# controller.net
KiCad netlist of a schematic drawn in EAGLE
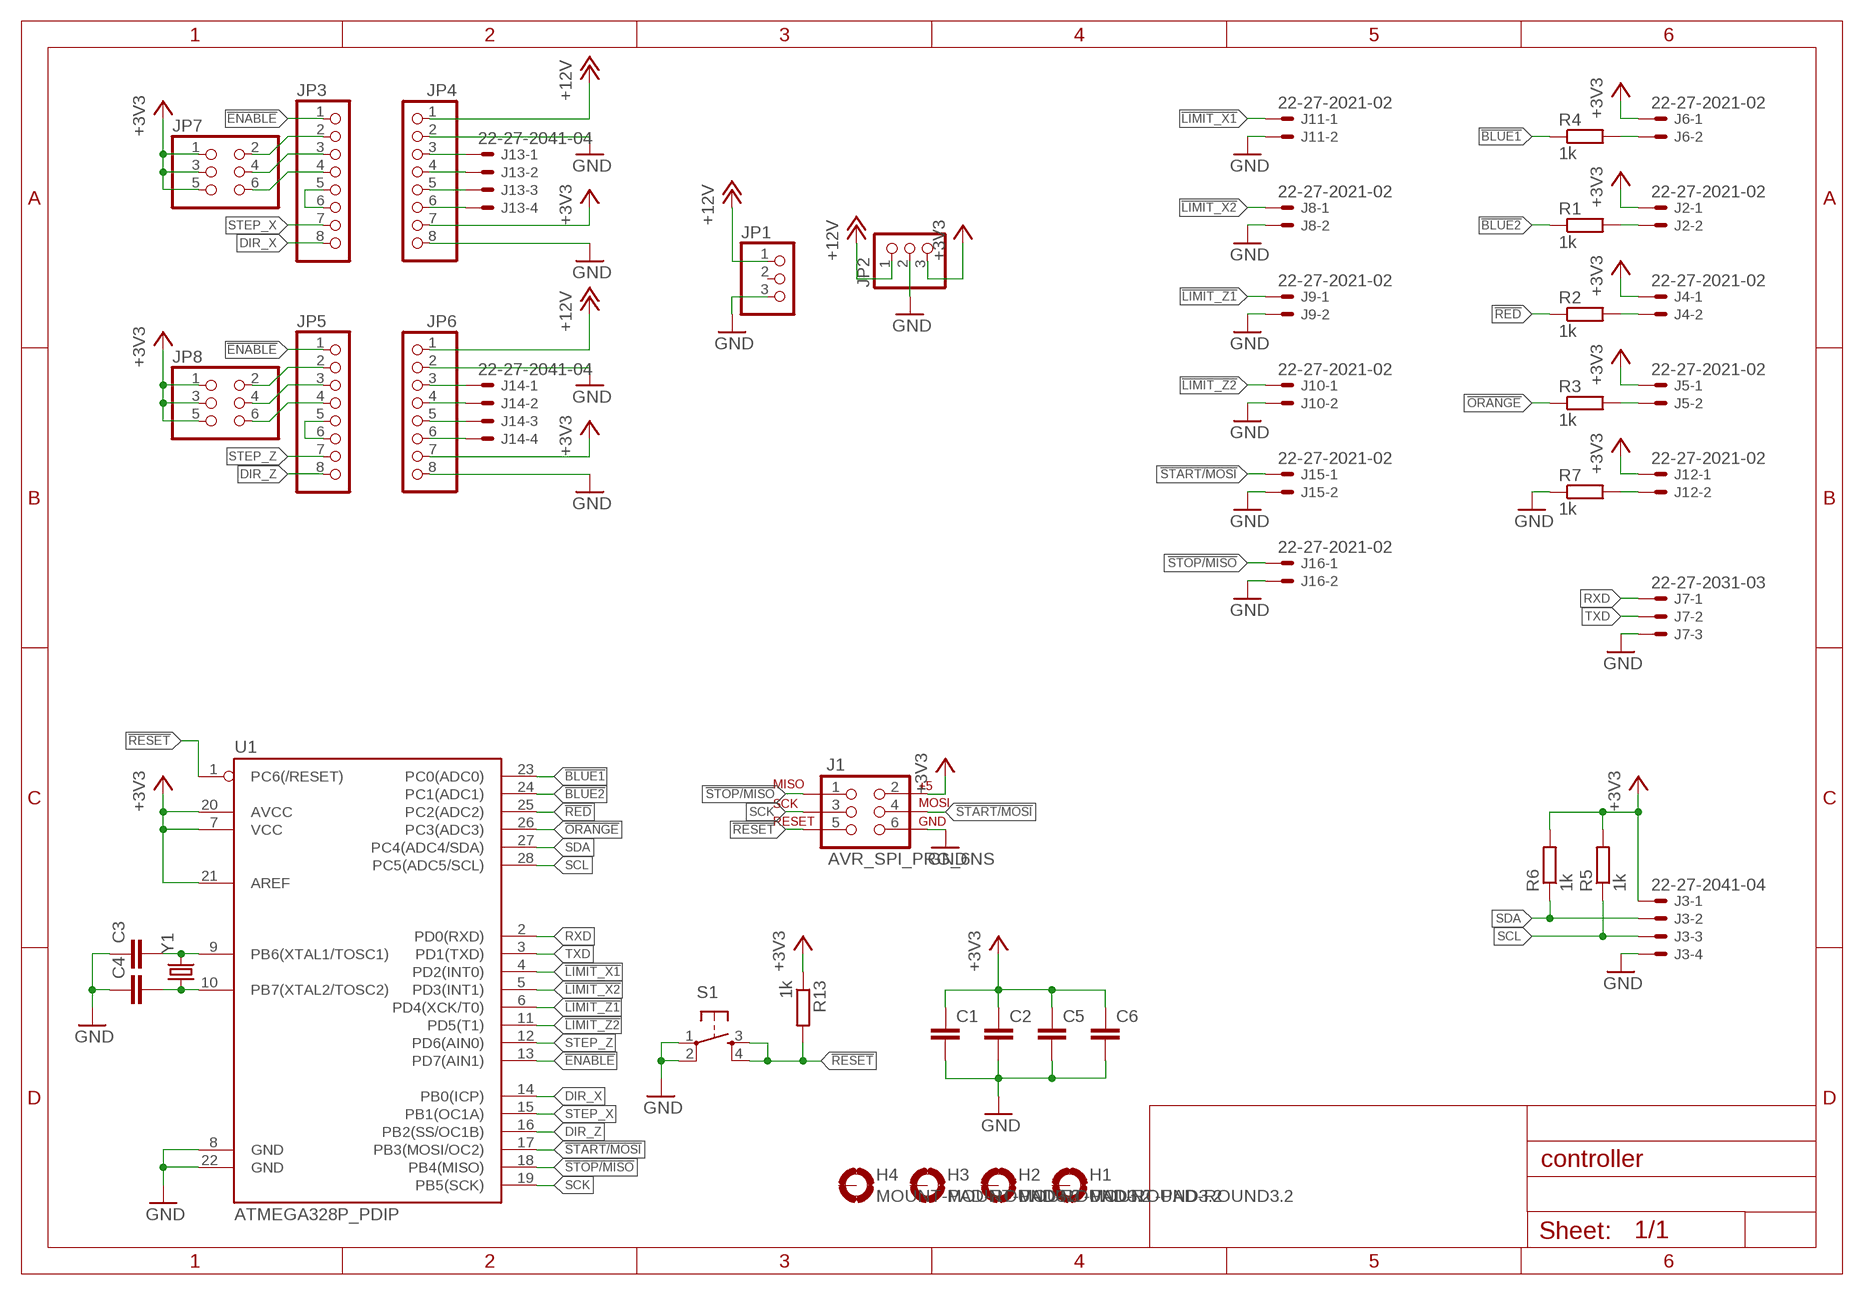
[diagram p0: schematic, sheet 1]

(export (version "E")
  (design (tool "Eeschema 10.0.6"))
  (components
    (comp (ref "C1")
      (value "C-EUC0603")
      (footprint "eagle-import:C0603")
      (libsource (lib "eagle-import") (part "C-EUC0603"))
    )
    (comp (ref "C2")
      (value "C-EUC0603")
      (footprint "eagle-import:C0603")
      (libsource (lib "eagle-import") (part "C-EUC0603"))
    )
    (comp (ref "C3")
      (value "C-EUC0603K")
      (footprint "eagle-import:C0603K")
      (libsource (lib "eagle-import") (part "C-EUC0603K"))
    )
    (comp (ref "C4")
      (value "C-EUC0603K")
      (footprint "eagle-import:C0603K")
      (libsource (lib "eagle-import") (part "C-EUC0603K"))
    )
    (comp (ref "C5")
      (value "C-EUC0603")
      (footprint "eagle-import:C0603")
      (libsource (lib "eagle-import") (part "C-EUC0603"))
    )
    (comp (ref "C6")
      (value "C-EUC0603")
      (footprint "eagle-import:C0603")
      (libsource (lib "eagle-import") (part "C-EUC0603"))
    )
    (comp (ref "H1")
      (value "MOUNT-PAD-ROUND3.2")
      (footprint "eagle-import:3,2-PAD")
      (libsource (lib "eagle-import") (part "MOUNT-PAD-ROUND3.2"))
    )
    (comp (ref "H2")
      (value "MOUNT-PAD-ROUND3.2")
      (footprint "eagle-import:3,2-PAD")
      (libsource (lib "eagle-import") (part "MOUNT-PAD-ROUND3.2"))
    )
    (comp (ref "H3")
      (value "MOUNT-PAD-ROUND3.2")
      (footprint "eagle-import:3,2-PAD")
      (libsource (lib "eagle-import") (part "MOUNT-PAD-ROUND3.2"))
    )
    (comp (ref "H4")
      (value "MOUNT-PAD-ROUND3.2")
      (footprint "eagle-import:3,2-PAD")
      (libsource (lib "eagle-import") (part "MOUNT-PAD-ROUND3.2"))
    )
    (comp (ref "J1")
      (value "AVR_SPI_PRG_6NS")
      (footprint "eagle-import:2X3-NS")
      (libsource (lib "eagle-import") (part "AVR_SPI_PRG_6NS"))
    )
    (comp (ref "J2")
      (value "22-27-2021-02")
      (footprint "eagle-import:6410-02")
      (libsource (lib "eagle-import") (part "22-?-0227-2021"))
    )
    (comp (ref "J3")
      (value "22-27-2041-04")
      (footprint "eagle-import:6410-04")
      (libsource (lib "eagle-import") (part "22-?-0427-2041"))
    )
    (comp (ref "J4")
      (value "22-27-2021-02")
      (footprint "eagle-import:6410-02")
      (libsource (lib "eagle-import") (part "22-?-0227-2021"))
    )
    (comp (ref "J5")
      (value "22-27-2021-02")
      (footprint "eagle-import:6410-02")
      (libsource (lib "eagle-import") (part "22-?-0227-2021"))
    )
    (comp (ref "J6")
      (value "22-27-2021-02")
      (footprint "eagle-import:6410-02")
      (libsource (lib "eagle-import") (part "22-?-0227-2021"))
    )
    (comp (ref "J7")
      (value "22-27-2031-03")
      (footprint "eagle-import:6410-03")
      (libsource (lib "eagle-import") (part "22-?-0327-2031"))
    )
    (comp (ref "J8")
      (value "22-27-2021-02")
      (footprint "eagle-import:6410-02")
      (libsource (lib "eagle-import") (part "22-?-0227-2021"))
    )
    (comp (ref "J9")
      (value "22-27-2021-02")
      (footprint "eagle-import:6410-02")
      (libsource (lib "eagle-import") (part "22-?-0227-2021"))
    )
    (comp (ref "J10")
      (value "22-27-2021-02")
      (footprint "eagle-import:6410-02")
      (libsource (lib "eagle-import") (part "22-?-0227-2021"))
    )
    (comp (ref "J11")
      (value "22-27-2021-02")
      (footprint "eagle-import:6410-02")
      (libsource (lib "eagle-import") (part "22-?-0227-2021"))
    )
    (comp (ref "J12")
      (value "22-27-2021-02")
      (footprint "eagle-import:6410-02")
      (libsource (lib "eagle-import") (part "22-?-0227-2021"))
    )
    (comp (ref "J13")
      (value "22-27-2041-04")
      (footprint "eagle-import:6410-04")
      (libsource (lib "eagle-import") (part "22-?-0427-2041"))
    )
    (comp (ref "J14")
      (value "22-27-2041-04")
      (footprint "eagle-import:6410-04")
      (libsource (lib "eagle-import") (part "22-?-0427-2041"))
    )
    (comp (ref "J15")
      (value "22-27-2021-02")
      (footprint "eagle-import:6410-02")
      (libsource (lib "eagle-import") (part "22-?-0227-2021"))
    )
    (comp (ref "J16")
      (value "22-27-2021-02")
      (footprint "eagle-import:6410-02")
      (libsource (lib "eagle-import") (part "22-?-0227-2021"))
    )
    (comp (ref "JP1")
      (value "PINHD-1X3")
      (footprint "eagle-import:1X03")
      (libsource (lib "eagle-import") (part "PINHD-1X3"))
    )
    (comp (ref "JP2")
      (value "PINHD-1X3")
      (footprint "eagle-import:1X03")
      (libsource (lib "eagle-import") (part "PINHD-1X3"))
    )
    (comp (ref "JP3")
      (value "PINHD-1X8")
      (footprint "eagle-import:1X08")
      (libsource (lib "eagle-import") (part "PINHD-1X8"))
    )
    (comp (ref "JP4")
      (value "PINHD-1X8")
      (footprint "eagle-import:1X08")
      (libsource (lib "eagle-import") (part "PINHD-1X8"))
    )
    (comp (ref "JP5")
      (value "PINHD-1X8")
      (footprint "eagle-import:1X08")
      (libsource (lib "eagle-import") (part "PINHD-1X8"))
    )
    (comp (ref "JP6")
      (value "PINHD-1X8")
      (footprint "eagle-import:1X08")
      (libsource (lib "eagle-import") (part "PINHD-1X8"))
    )
    (comp (ref "JP7")
      (value "PINHD-2X3")
      (footprint "eagle-import:2X03")
      (libsource (lib "eagle-import") (part "PINHD-2X3"))
    )
    (comp (ref "JP8")
      (value "PINHD-2X3")
      (footprint "eagle-import:2X03")
      (libsource (lib "eagle-import") (part "PINHD-2X3"))
    )
    (comp (ref "R1")
      (value "1k")
      (footprint "eagle-import:R0603")
      (libsource (lib "eagle-import") (part "R-EU_R0603"))
    )
    (comp (ref "R2")
      (value "1k")
      (footprint "eagle-import:R0603")
      (libsource (lib "eagle-import") (part "R-EU_R0603"))
    )
    (comp (ref "R3")
      (value "1k")
      (footprint "eagle-import:R0603")
      (libsource (lib "eagle-import") (part "R-EU_R0603"))
    )
    (comp (ref "R4")
      (value "1k")
      (footprint "eagle-import:R0603")
      (libsource (lib "eagle-import") (part "R-EU_R0603"))
    )
    (comp (ref "R5")
      (value "1k")
      (footprint "eagle-import:R0603")
      (libsource (lib "eagle-import") (part "R-EU_R0603"))
    )
    (comp (ref "R6")
      (value "1k")
      (footprint "eagle-import:R0603")
      (libsource (lib "eagle-import") (part "R-EU_R0603"))
    )
    (comp (ref "R7")
      (value "1k")
      (footprint "eagle-import:R0603")
      (libsource (lib "eagle-import") (part "R-EU_R0603"))
    )
    (comp (ref "R13")
      (value "1k")
      (footprint "eagle-import:R0603")
      (libsource (lib "eagle-import") (part "R-EU_R0603"))
    )
    (comp (ref "S1")
      (value "TAC_SWITCHPTH")
      (footprint "eagle-import:TACTILE-PTH")
      (libsource (lib "eagle-import") (part "TAC_SWITCHPTH"))
    )
    (comp (ref "U1")
      (value "ATMEGA328P_PDIP")
      (footprint "eagle-import:DIL28-3")
      (libsource (lib "eagle-import") (part "ATMEGA328P_PDIP"))
    )
    (comp (ref "Y1")
      (value "CRYSTALHC49UV")
      (footprint "eagle-import:HC49U-V")
      (libsource (lib "eagle-import") (part "CRYSTALHC49UV"))
    )
  )
  (nets
    (net (code "1") (name "+3V3") (class "Default")
      (node (ref "C1") (pin "1") (pinfunction "1_1") (pintype "passive"))
      (node (ref "C2") (pin "1") (pinfunction "1_1") (pintype "passive"))
      (node (ref "C5") (pin "1") (pinfunction "1_1") (pintype "passive"))
      (node (ref "C6") (pin "1") (pinfunction "1_1") (pintype "passive"))
      (node (ref "J1") (pin "2") (pinfunction "2_2") (pintype "passive"))
      (node (ref "J12") (pin "1") (pinfunction "S_1") (pintype "passive"))
      (node (ref "J2") (pin "1") (pinfunction "S_1") (pintype "passive"))
      (node (ref "J3") (pin "1") (pinfunction "S_1") (pintype "passive"))
      (node (ref "J4") (pin "1") (pinfunction "S_1") (pintype "passive"))
      (node (ref "J5") (pin "1") (pinfunction "S_1") (pintype "passive"))
      (node (ref "J6") (pin "1") (pinfunction "S_1") (pintype "passive"))
      (node (ref "JP2") (pin "3") (pinfunction "3_3") (pintype "passive"))
      (node (ref "JP4") (pin "7") (pinfunction "7_7") (pintype "passive"))
      (node (ref "JP6") (pin "7") (pinfunction "7_7") (pintype "passive"))
      (node (ref "JP7") (pin "1") (pinfunction "1_1") (pintype "passive"))
      (node (ref "JP7") (pin "3") (pinfunction "3_3") (pintype "passive"))
      (node (ref "JP7") (pin "5") (pinfunction "5_5") (pintype "passive"))
      (node (ref "JP8") (pin "1") (pinfunction "1_1") (pintype "passive"))
      (node (ref "JP8") (pin "3") (pinfunction "3_3") (pintype "passive"))
      (node (ref "JP8") (pin "5") (pinfunction "5_5") (pintype "passive"))
      (node (ref "R13") (pin "1") (pinfunction "1_1") (pintype "passive"))
      (node (ref "R5") (pin "2") (pinfunction "2_2") (pintype "passive"))
      (node (ref "R6") (pin "2") (pinfunction "2_2") (pintype "passive"))
      (node (ref "U1") (pin "20") (pinfunction "AVCC_20") (pintype "bidirectional"))
      (node (ref "U1") (pin "21") (pinfunction "AREF_21") (pintype "bidirectional"))
      (node (ref "U1") (pin "7") (pinfunction "VCC_7") (pintype "bidirectional"))
    )
    (net (code "2") (name "+12V") (class "Default")
      (node (ref "JP1") (pin "1") (pinfunction "1_1") (pintype "passive"))
      (node (ref "JP2") (pin "1") (pinfunction "1_1") (pintype "passive"))
      (node (ref "JP4") (pin "1") (pinfunction "1_1") (pintype "passive"))
      (node (ref "JP6") (pin "1") (pinfunction "1_1") (pintype "passive"))
    )
    (net (code "3") (name "/~{BLUE1}") (class "Default")
      (node (ref "R4") (pin "1") (pinfunction "1_1") (pintype "passive"))
      (node (ref "U1") (pin "23") (pinfunction "PC0(ADC0)_23") (pintype "bidirectional"))
    )
    (net (code "4") (name "/~{BLUE2}") (class "Default")
      (node (ref "R1") (pin "1") (pinfunction "1_1") (pintype "passive"))
      (node (ref "U1") (pin "24") (pinfunction "PC1(ADC1)_24") (pintype "bidirectional"))
    )
    (net (code "5") (name "/~{ENABLE}") (class "Default")
      (node (ref "JP3") (pin "1") (pinfunction "1_1") (pintype "passive"))
      (node (ref "JP5") (pin "1") (pinfunction "1_1") (pintype "passive"))
      (node (ref "U1") (pin "13") (pinfunction "PD7(AIN1)_13") (pintype "bidirectional"))
    )
    (net (code "6") (name "/~{LIMIT_X1}") (class "Default")
      (node (ref "J11") (pin "1") (pinfunction "S_1") (pintype "passive"))
      (node (ref "U1") (pin "4") (pinfunction "PD2(INT0)_4") (pintype "bidirectional"))
    )
    (net (code "7") (name "/~{LIMIT_X2}") (class "Default")
      (node (ref "J8") (pin "1") (pinfunction "S_1") (pintype "passive"))
      (node (ref "U1") (pin "5") (pinfunction "PD3(INT1)_5") (pintype "bidirectional"))
    )
    (net (code "8") (name "/~{LIMIT_Z1}") (class "Default")
      (node (ref "J9") (pin "1") (pinfunction "S_1") (pintype "passive"))
      (node (ref "U1") (pin "6") (pinfunction "PD4(XCK/T0)_6") (pintype "bidirectional"))
    )
    (net (code "9") (name "/~{LIMIT_Z2}") (class "Default")
      (node (ref "J10") (pin "1") (pinfunction "S_1") (pintype "passive"))
      (node (ref "U1") (pin "11") (pinfunction "PD5(T1)_11") (pintype "bidirectional"))
    )
    (net (code "10") (name "/~{ORANGE}") (class "Default")
      (node (ref "R3") (pin "1") (pinfunction "1_1") (pintype "passive"))
      (node (ref "U1") (pin "26") (pinfunction "PC3(ADC3)_26") (pintype "bidirectional"))
    )
    (net (code "11") (name "/~{RED}") (class "Default")
      (node (ref "R2") (pin "1") (pinfunction "1_1") (pintype "passive"))
      (node (ref "U1") (pin "25") (pinfunction "PC2(ADC2)_25") (pintype "bidirectional"))
    )
    (net (code "12") (name "/~{RESET}") (class "Default")
      (node (ref "J1") (pin "5") (pinfunction "5_5") (pintype "passive"))
      (node (ref "R13") (pin "2") (pinfunction "2_2") (pintype "passive"))
      (node (ref "S1") (pin "3") (pinfunction "3_3") (pintype "passive"))
      (node (ref "S1") (pin "4") (pinfunction "4_4") (pintype "passive"))
      (node (ref "U1") (pin "1") (pinfunction "PC6(/RESET)_1") (pintype "bidirectional"))
    )
    (net (code "13") (name "/~{START{slash}MOSI}") (class "Default")
      (node (ref "J1") (pin "4") (pinfunction "4_4") (pintype "passive"))
      (node (ref "J15") (pin "1") (pinfunction "S_1") (pintype "passive"))
      (node (ref "U1") (pin "17") (pinfunction "PB3(MOSI/OC2)_17") (pintype "bidirectional"))
    )
    (net (code "14") (name "/~{STOP{slash}MISO}") (class "Default")
      (node (ref "J1") (pin "1") (pinfunction "1_1") (pintype "passive"))
      (node (ref "J16") (pin "1") (pinfunction "S_1") (pintype "passive"))
      (node (ref "U1") (pin "18") (pinfunction "PB4(MISO)_18") (pintype "bidirectional"))
    )
    (net (code "15") (name "DIR_X") (class "Default")
      (node (ref "JP3") (pin "8") (pinfunction "8_8") (pintype "passive"))
      (node (ref "U1") (pin "14") (pinfunction "PB0(ICP)_14") (pintype "bidirectional"))
    )
    (net (code "16") (name "DIR_Z") (class "Default")
      (node (ref "JP5") (pin "8") (pinfunction "8_8") (pintype "passive"))
      (node (ref "U1") (pin "16") (pinfunction "PB2(SS/OC1B)_16") (pintype "bidirectional"))
    )
    (net (code "17") (name "GND") (class "Default")
      (node (ref "C1") (pin "2") (pinfunction "2_2") (pintype "passive"))
      (node (ref "C2") (pin "2") (pinfunction "2_2") (pintype "passive"))
      (node (ref "C3") (pin "1") (pinfunction "1_1") (pintype "passive"))
      (node (ref "C4") (pin "1") (pinfunction "1_1") (pintype "passive"))
      (node (ref "C5") (pin "2") (pinfunction "2_2") (pintype "passive"))
      (node (ref "C6") (pin "2") (pinfunction "2_2") (pintype "passive"))
      (node (ref "J1") (pin "6") (pinfunction "6_6") (pintype "passive"))
      (node (ref "J10") (pin "2") (pinfunction "S_2") (pintype "passive"))
      (node (ref "J11") (pin "2") (pinfunction "S_2") (pintype "passive"))
      (node (ref "J15") (pin "2") (pinfunction "S_2") (pintype "passive"))
      (node (ref "J16") (pin "2") (pinfunction "S_2") (pintype "passive"))
      (node (ref "J3") (pin "4") (pinfunction "S_4") (pintype "passive"))
      (node (ref "J7") (pin "3") (pinfunction "S_3") (pintype "passive"))
      (node (ref "J8") (pin "2") (pinfunction "S_2") (pintype "passive"))
      (node (ref "J9") (pin "2") (pinfunction "S_2") (pintype "passive"))
      (node (ref "JP1") (pin "3") (pinfunction "3_3") (pintype "passive"))
      (node (ref "JP2") (pin "2") (pinfunction "2_2") (pintype "passive"))
      (node (ref "JP4") (pin "2") (pinfunction "2_2") (pintype "passive"))
      (node (ref "JP4") (pin "8") (pinfunction "8_8") (pintype "passive"))
      (node (ref "JP6") (pin "2") (pinfunction "2_2") (pintype "passive"))
      (node (ref "JP6") (pin "8") (pinfunction "8_8") (pintype "passive"))
      (node (ref "R7") (pin "1") (pinfunction "1_1") (pintype "passive"))
      (node (ref "S1") (pin "1") (pinfunction "1_1") (pintype "passive"))
      (node (ref "S1") (pin "2") (pinfunction "2_2") (pintype "passive"))
      (node (ref "U1") (pin "22") (pinfunction "GND_22") (pintype "bidirectional"))
      (node (ref "U1") (pin "8") (pinfunction "GND_8") (pintype "bidirectional"))
    )
    (net (code "18") (name "Net-(J2B-S)") (class "Default")
      (node (ref "J2") (pin "2") (pinfunction "S_2") (pintype "passive"))
      (node (ref "R1") (pin "2") (pinfunction "2_2") (pintype "passive"))
    )
    (net (code "19") (name "Net-(J4B-S)") (class "Default")
      (node (ref "J4") (pin "2") (pinfunction "S_2") (pintype "passive"))
      (node (ref "R2") (pin "2") (pinfunction "2_2") (pintype "passive"))
    )
    (net (code "20") (name "Net-(J5B-S)") (class "Default")
      (node (ref "J5") (pin "2") (pinfunction "S_2") (pintype "passive"))
      (node (ref "R3") (pin "2") (pinfunction "2_2") (pintype "passive"))
    )
    (net (code "21") (name "Net-(J6B-S)") (class "Default")
      (node (ref "J6") (pin "2") (pinfunction "S_2") (pintype "passive"))
      (node (ref "R4") (pin "2") (pinfunction "2_2") (pintype "passive"))
    )
    (net (code "22") (name "Net-(J12B-S)") (class "Default")
      (node (ref "J12") (pin "2") (pinfunction "S_2") (pintype "passive"))
      (node (ref "R7") (pin "2") (pinfunction "2_2") (pintype "passive"))
    )
    (net (code "23") (name "Net-(J13A-S)") (class "Default")
      (node (ref "J13") (pin "1") (pinfunction "S_1") (pintype "passive"))
      (node (ref "JP4") (pin "3") (pinfunction "3_3") (pintype "passive"))
    )
    (net (code "24") (name "Net-(J13B-S)") (class "Default")
      (node (ref "J13") (pin "2") (pinfunction "S_2") (pintype "passive"))
      (node (ref "JP4") (pin "4") (pinfunction "4_4") (pintype "passive"))
    )
    (net (code "25") (name "Net-(J13C-S)") (class "Default")
      (node (ref "J13") (pin "3") (pinfunction "S_3") (pintype "passive"))
      (node (ref "JP4") (pin "5") (pinfunction "5_5") (pintype "passive"))
    )
    (net (code "26") (name "Net-(J13D-S)") (class "Default")
      (node (ref "J13") (pin "4") (pinfunction "S_4") (pintype "passive"))
      (node (ref "JP4") (pin "6") (pinfunction "6_6") (pintype "passive"))
    )
    (net (code "27") (name "Net-(J14A-S)") (class "Default")
      (node (ref "J14") (pin "1") (pinfunction "S_1") (pintype "passive"))
      (node (ref "JP6") (pin "3") (pinfunction "3_3") (pintype "passive"))
    )
    (net (code "28") (name "Net-(J14B-S)") (class "Default")
      (node (ref "J14") (pin "2") (pinfunction "S_2") (pintype "passive"))
      (node (ref "JP6") (pin "4") (pinfunction "4_4") (pintype "passive"))
    )
    (net (code "29") (name "Net-(J14C-S)") (class "Default")
      (node (ref "J14") (pin "3") (pinfunction "S_3") (pintype "passive"))
      (node (ref "JP6") (pin "5") (pinfunction "5_5") (pintype "passive"))
    )
    (net (code "30") (name "Net-(J14D-S)") (class "Default")
      (node (ref "J14") (pin "4") (pinfunction "S_4") (pintype "passive"))
      (node (ref "JP6") (pin "6") (pinfunction "6_6") (pintype "passive"))
    )
    (net (code "31") (name "Net-(JP3-Pad2)") (class "Default")
      (node (ref "JP3") (pin "2") (pinfunction "2_2") (pintype "passive"))
      (node (ref "JP7") (pin "2") (pinfunction "2_2") (pintype "passive"))
    )
    (net (code "32") (name "Net-(JP3-Pad3)") (class "Default")
      (node (ref "JP3") (pin "3") (pinfunction "3_3") (pintype "passive"))
      (node (ref "JP7") (pin "4") (pinfunction "4_4") (pintype "passive"))
    )
    (net (code "33") (name "Net-(JP3-Pad4)") (class "Default")
      (node (ref "JP3") (pin "4") (pinfunction "4_4") (pintype "passive"))
      (node (ref "JP7") (pin "6") (pinfunction "6_6") (pintype "passive"))
    )
    (net (code "34") (name "Net-(JP3-Pad5)") (class "Default")
      (node (ref "JP3") (pin "5") (pinfunction "5_5") (pintype "passive"))
      (node (ref "JP3") (pin "6") (pinfunction "6_6") (pintype "passive"))
    )
    (net (code "35") (name "Net-(JP5-Pad2)") (class "Default")
      (node (ref "JP5") (pin "2") (pinfunction "2_2") (pintype "passive"))
      (node (ref "JP8") (pin "2") (pinfunction "2_2") (pintype "passive"))
    )
    (net (code "36") (name "Net-(JP5-Pad3)") (class "Default")
      (node (ref "JP5") (pin "3") (pinfunction "3_3") (pintype "passive"))
      (node (ref "JP8") (pin "4") (pinfunction "4_4") (pintype "passive"))
    )
    (net (code "37") (name "Net-(JP5-Pad4)") (class "Default")
      (node (ref "JP5") (pin "4") (pinfunction "4_4") (pintype "passive"))
      (node (ref "JP8") (pin "6") (pinfunction "6_6") (pintype "passive"))
    )
    (net (code "38") (name "Net-(JP5-Pad5)") (class "Default")
      (node (ref "JP5") (pin "5") (pinfunction "5_5") (pintype "passive"))
      (node (ref "JP5") (pin "6") (pinfunction "6_6") (pintype "passive"))
    )
    (net (code "39") (name "Net-(U1-PB6(XTAL1{slash}TOSC1))") (class "Default")
      (node (ref "C3") (pin "2") (pinfunction "2_2") (pintype "passive"))
      (node (ref "U1") (pin "9") (pinfunction "PB6(XTAL1/TOSC1)_9") (pintype "bidirectional"))
      (node (ref "Y1") (pin "2") (pinfunction "2_2") (pintype "passive"))
    )
    (net (code "40") (name "Net-(U1-PB7(XTAL2{slash}TOSC2))") (class "Default")
      (node (ref "C4") (pin "2") (pinfunction "2_2") (pintype "passive"))
      (node (ref "U1") (pin "10") (pinfunction "PB7(XTAL2/TOSC2)_10") (pintype "bidirectional"))
      (node (ref "Y1") (pin "1") (pinfunction "1_1") (pintype "passive"))
    )
    (net (code "41") (name "RXD") (class "Default")
      (node (ref "J7") (pin "1") (pinfunction "S_1") (pintype "passive"))
      (node (ref "U1") (pin "2") (pinfunction "PD0(RXD)_2") (pintype "bidirectional"))
    )
    (net (code "42") (name "SCK") (class "Default")
      (node (ref "J1") (pin "3") (pinfunction "3_3") (pintype "passive"))
      (node (ref "U1") (pin "19") (pinfunction "PB5(SCK)_19") (pintype "bidirectional"))
    )
    (net (code "43") (name "SCL") (class "Default")
      (node (ref "J3") (pin "3") (pinfunction "S_3") (pintype "passive"))
      (node (ref "R5") (pin "1") (pinfunction "1_1") (pintype "passive"))
      (node (ref "U1") (pin "28") (pinfunction "PC5(ADC5/SCL)_28") (pintype "bidirectional"))
    )
    (net (code "44") (name "SDA") (class "Default")
      (node (ref "J3") (pin "2") (pinfunction "S_2") (pintype "passive"))
      (node (ref "R6") (pin "1") (pinfunction "1_1") (pintype "passive"))
      (node (ref "U1") (pin "27") (pinfunction "PC4(ADC4/SDA)_27") (pintype "bidirectional"))
    )
    (net (code "45") (name "STEP_X") (class "Default")
      (node (ref "JP3") (pin "7") (pinfunction "7_7") (pintype "passive"))
      (node (ref "U1") (pin "15") (pinfunction "PB1(OC1A)_15") (pintype "bidirectional"))
    )
    (net (code "46") (name "STEP_Z") (class "Default")
      (node (ref "JP5") (pin "7") (pinfunction "7_7") (pintype "passive"))
      (node (ref "U1") (pin "12") (pinfunction "PD6(AIN0)_12") (pintype "bidirectional"))
    )
    (net (code "47") (name "TXD") (class "Default")
      (node (ref "J7") (pin "2") (pinfunction "S_2") (pintype "passive"))
      (node (ref "U1") (pin "3") (pinfunction "PD1(TXD)_3") (pintype "bidirectional"))
    )
    (net (code "48") (name "unconnected-(H1-MOUNT-PadB3,2)") (class "Default")
      (node (ref "H1") (pin "B3,2") (pinfunction "MOUNT_B3,2") (pintype "passive"))
    )
    (net (code "49") (name "unconnected-(H2-MOUNT-PadB3,2)") (class "Default")
      (node (ref "H2") (pin "B3,2") (pinfunction "MOUNT_B3,2") (pintype "passive"))
    )
    (net (code "50") (name "unconnected-(H3-MOUNT-PadB3,2)") (class "Default")
      (node (ref "H3") (pin "B3,2") (pinfunction "MOUNT_B3,2") (pintype "passive"))
    )
    (net (code "51") (name "unconnected-(H4-MOUNT-PadB3,2)") (class "Default")
      (node (ref "H4") (pin "B3,2") (pinfunction "MOUNT_B3,2") (pintype "passive"))
    )
    (net (code "52") (name "unconnected-(JP1-Pad2)") (class "Default")
      (node (ref "JP1") (pin "2") (pinfunction "2_2") (pintype "passive"))
    )
  )
)
